# ControlBoardConnector.net
KiCad netlist of a schematic drawn in Altium Designer
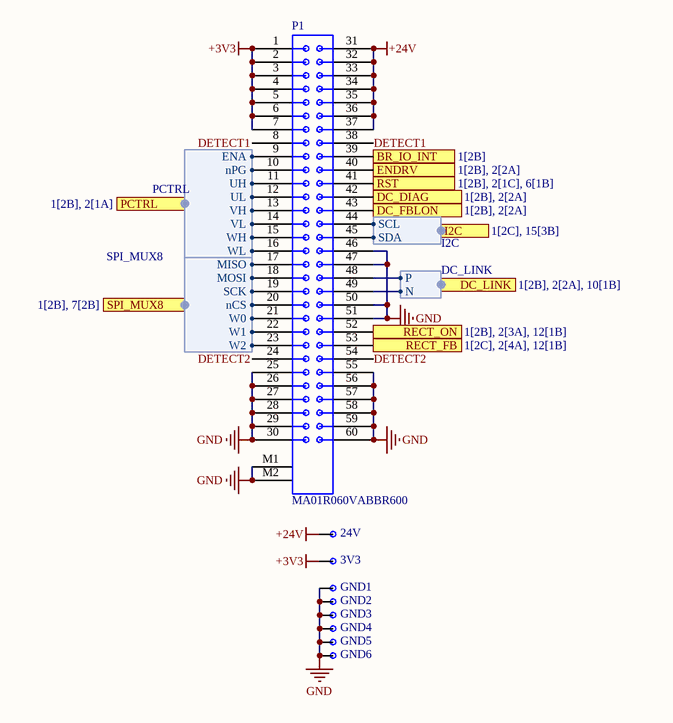
[diagram p0: ControlBoardConnector.SchDoc]

(export (version "E")
  (design (tool "Eeschema 10.0.6"))
  (components
    (comp (ref "3V3")
      (value "Testpoint")
      (footprint "Testpoint-Footprint-1")
      (libsource (lib "Saule S.A") (part "Testpoint"))
    )
    (comp (ref "24V")
      (value "Testpoint")
      (footprint "Testpoint-Footprint-1")
      (libsource (lib "Saule S.A") (part "Testpoint"))
    )
    (comp (ref "GND1")
      (value "Testpoint")
      (footprint "Testpoint-Footprint-1")
      (libsource (lib "Saule S.A") (part "Testpoint"))
    )
    (comp (ref "GND2")
      (value "Testpoint")
      (footprint "Testpoint-Footprint-1")
      (libsource (lib "Saule S.A") (part "Testpoint"))
    )
    (comp (ref "GND3")
      (value "Testpoint")
      (footprint "Testpoint-Footprint-1")
      (libsource (lib "Saule S.A") (part "Testpoint"))
    )
    (comp (ref "GND4")
      (value "Testpoint")
      (footprint "Testpoint-Footprint-1")
      (libsource (lib "Saule S.A") (part "Testpoint"))
    )
    (comp (ref "GND5")
      (value "Testpoint")
      (footprint "Testpoint-Footprint-1")
      (libsource (lib "Saule S.A") (part "Testpoint"))
    )
    (comp (ref "GND6")
      (value "Testpoint")
      (footprint "Testpoint-Footprint-1")
      (libsource (lib "Saule S.A") (part "Testpoint"))
    )
    (comp (ref "P1")
      (value "MA01R060VABBR600")
      (footprint "MA01F060VABBR300-Footprint-1")
      (description "Right-angle Dual Port D-Sub Connector")
      (libsource (lib "Saule S.A") (part "MA01F060VABBR300-Symbol-1"))
    )
  )
  (nets
    (net (code "5") (name "+3V3") (class "Default")
      (node (ref "3V3") (pin "1") (pinfunction "1_1") (pintype "passive"))
      (node (ref "P1") (pin "1") (pinfunction "1_1") (pintype "passive"))
      (node (ref "P1") (pin "2") (pinfunction "2_2") (pintype "passive"))
      (node (ref "P1") (pin "3") (pinfunction "3_3") (pintype "passive"))
      (node (ref "P1") (pin "4") (pinfunction "4_4") (pintype "passive"))
      (node (ref "P1") (pin "5") (pinfunction "5_5") (pintype "passive"))
      (node (ref "P1") (pin "6") (pinfunction "6_6") (pintype "passive"))
      (node (ref "P1") (pin "7") (pinfunction "7_7") (pintype "passive"))
    )
    (net (code "6") (name "+24V") (class "Default")
      (node (ref "24V") (pin "1") (pinfunction "1_1") (pintype "passive"))
      (node (ref "P1") (pin "31") (pinfunction "31_31") (pintype "passive"))
      (node (ref "P1") (pin "32") (pinfunction "32_32") (pintype "passive"))
      (node (ref "P1") (pin "33") (pinfunction "33_33") (pintype "passive"))
      (node (ref "P1") (pin "34") (pinfunction "34_34") (pintype "passive"))
      (node (ref "P1") (pin "35") (pinfunction "35_35") (pintype "passive"))
      (node (ref "P1") (pin "36") (pinfunction "36_36") (pintype "passive"))
      (node (ref "P1") (pin "37") (pinfunction "37_37") (pintype "passive"))
    )
    (net (code "7") (name "/BR_IO_INT") (class "Default")
      (node (ref "P1") (pin "39") (pinfunction "39_39") (pintype "passive"))
    )
    (net (code "8") (name "/DC_DIAG") (class "Default")
      (node (ref "P1") (pin "42") (pinfunction "42_42") (pintype "passive"))
    )
    (net (code "9") (name "/DC_FBLON") (class "Default")
      (node (ref "P1") (pin "43") (pinfunction "43_43") (pintype "passive"))
    )
    (net (code "10") (name "/DETECT1") (class "Default")
      (node (ref "P1") (pin "38") (pinfunction "38_38") (pintype "passive"))
      (node (ref "P1") (pin "8") (pinfunction "8_8") (pintype "passive"))
    )
    (net (code "11") (name "/DETECT2") (class "Default")
      (node (ref "P1") (pin "24") (pinfunction "24_24") (pintype "passive"))
      (node (ref "P1") (pin "54") (pinfunction "54_54") (pintype "passive"))
    )
    (net (code "12") (name "/ENA") (class "Default")
      (node (ref "P1") (pin "9") (pinfunction "9_9") (pintype "passive"))
    )
    (net (code "13") (name "/ENDRV") (class "Default")
      (node (ref "P1") (pin "40") (pinfunction "40_40") (pintype "passive"))
    )
    (net (code "14") (name "/MISO") (class "Default")
      (node (ref "P1") (pin "17") (pinfunction "17_17") (pintype "passive"))
    )
    (net (code "15") (name "/MOSI") (class "Default")
      (node (ref "P1") (pin "18") (pinfunction "18_18") (pintype "passive"))
    )
    (net (code "16") (name "/N") (class "Default")
      (node (ref "P1") (pin "49") (pinfunction "49_49") (pintype "passive"))
    )
    (net (code "17") (name "/P") (class "Default")
      (node (ref "P1") (pin "48") (pinfunction "48_48") (pintype "passive"))
    )
    (net (code "18") (name "/RECT_FB") (class "Default")
      (node (ref "P1") (pin "53") (pinfunction "53_53") (pintype "passive"))
    )
    (net (code "19") (name "/RECT_ON") (class "Default")
      (node (ref "P1") (pin "52") (pinfunction "52_52") (pintype "passive"))
    )
    (net (code "20") (name "/RST") (class "Default")
      (node (ref "P1") (pin "41") (pinfunction "41_41") (pintype "passive"))
    )
    (net (code "21") (name "/SCK") (class "Default")
      (node (ref "P1") (pin "19") (pinfunction "19_19") (pintype "passive"))
    )
    (net (code "22") (name "/SCL") (class "Default")
      (node (ref "P1") (pin "44") (pinfunction "44_44") (pintype "passive"))
    )
    (net (code "23") (name "/SDA") (class "Default")
      (node (ref "P1") (pin "45") (pinfunction "45_45") (pintype "passive"))
    )
    (net (code "24") (name "/UH") (class "Default")
      (node (ref "P1") (pin "11") (pinfunction "11_11") (pintype "passive"))
    )
    (net (code "25") (name "/UL") (class "Default")
      (node (ref "P1") (pin "12") (pinfunction "12_12") (pintype "passive"))
    )
    (net (code "26") (name "/VH") (class "Default")
      (node (ref "P1") (pin "13") (pinfunction "13_13") (pintype "passive"))
    )
    (net (code "27") (name "/VL") (class "Default")
      (node (ref "P1") (pin "14") (pinfunction "14_14") (pintype "passive"))
    )
    (net (code "28") (name "/W0") (class "Default")
      (node (ref "P1") (pin "21") (pinfunction "21_21") (pintype "passive"))
    )
    (net (code "29") (name "/W1") (class "Default")
      (node (ref "P1") (pin "22") (pinfunction "22_22") (pintype "passive"))
    )
    (net (code "30") (name "/W2") (class "Default")
      (node (ref "P1") (pin "23") (pinfunction "23_23") (pintype "passive"))
    )
    (net (code "31") (name "/WH") (class "Default")
      (node (ref "P1") (pin "15") (pinfunction "15_15") (pintype "passive"))
    )
    (net (code "32") (name "/WL") (class "Default")
      (node (ref "P1") (pin "16") (pinfunction "16_16") (pintype "passive"))
    )
    (net (code "33") (name "/nCS") (class "Default")
      (node (ref "P1") (pin "20") (pinfunction "20_20") (pintype "passive"))
    )
    (net (code "34") (name "/nPG") (class "Default")
      (node (ref "P1") (pin "10") (pinfunction "10_10") (pintype "passive"))
    )
    (net (code "39") (name "GND") (class "Default")
      (node (ref "GND1") (pin "1") (pinfunction "1_1") (pintype "passive"))
      (node (ref "GND2") (pin "1") (pinfunction "1_1") (pintype "passive"))
      (node (ref "GND3") (pin "1") (pinfunction "1_1") (pintype "passive"))
      (node (ref "GND4") (pin "1") (pinfunction "1_1") (pintype "passive"))
      (node (ref "GND5") (pin "1") (pinfunction "1_1") (pintype "passive"))
      (node (ref "GND6") (pin "1") (pinfunction "1_1") (pintype "passive"))
      (node (ref "P1") (pin "25") (pinfunction "25_25") (pintype "passive"))
      (node (ref "P1") (pin "26") (pinfunction "26_26") (pintype "passive"))
      (node (ref "P1") (pin "27") (pinfunction "27_27") (pintype "passive"))
      (node (ref "P1") (pin "28") (pinfunction "28_28") (pintype "passive"))
      (node (ref "P1") (pin "29") (pinfunction "29_29") (pintype "passive"))
      (node (ref "P1") (pin "30") (pinfunction "30_30") (pintype "passive"))
      (node (ref "P1") (pin "46") (pinfunction "46_46") (pintype "passive"))
      (node (ref "P1") (pin "47") (pinfunction "47_47") (pintype "passive"))
      (node (ref "P1") (pin "50") (pinfunction "50_50") (pintype "passive"))
      (node (ref "P1") (pin "51") (pinfunction "51_51") (pintype "passive"))
      (node (ref "P1") (pin "55") (pinfunction "55_55") (pintype "passive"))
      (node (ref "P1") (pin "56") (pinfunction "56_56") (pintype "passive"))
      (node (ref "P1") (pin "57") (pinfunction "57_57") (pintype "passive"))
      (node (ref "P1") (pin "58") (pinfunction "58_58") (pintype "passive"))
      (node (ref "P1") (pin "59") (pinfunction "59_59") (pintype "passive"))
      (node (ref "P1") (pin "60") (pinfunction "60_60") (pintype "passive"))
      (node (ref "P1") (pin "M1") (pinfunction "M1_M1") (pintype "passive"))
      (node (ref "P1") (pin "M2") (pinfunction "M2_M2") (pintype "passive"))
    )
  )
)
